# 2_Microcontrolador.net
KiCad netlist of a schematic drawn in Altium Designer
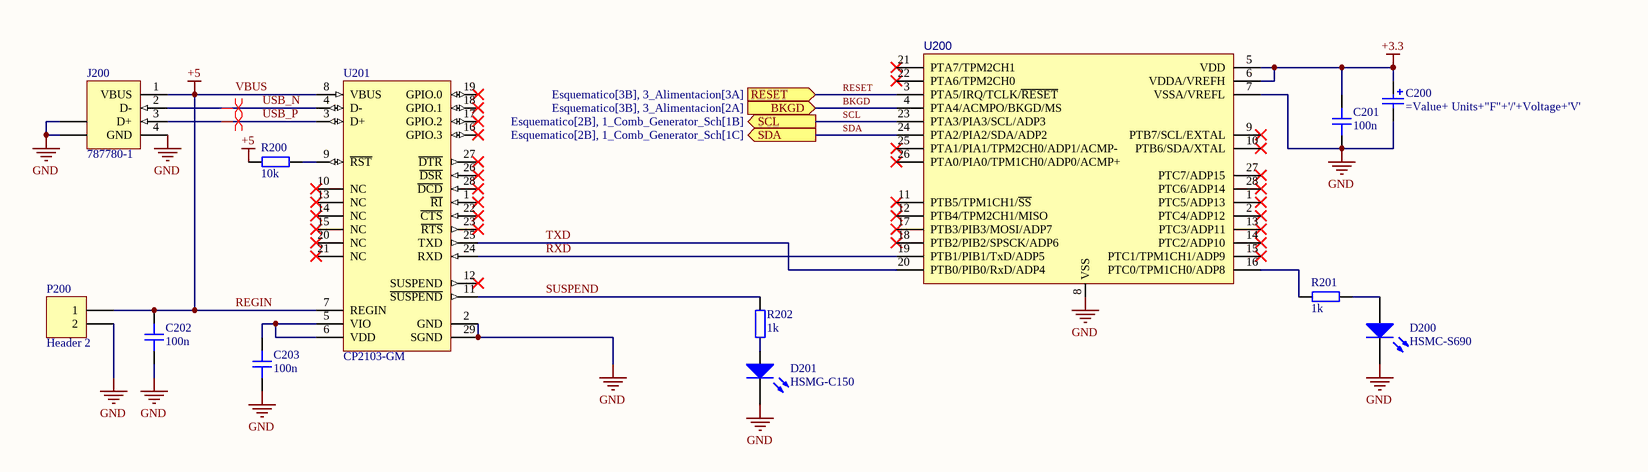
[diagram p0: 2_Microcontrolador.SchDoc]

(export (version "E")
  (design (tool "Eeschema 10.0.6"))
  (components
    (comp (ref "C200")
      (value "47u/16V")
      (footprint "C SIZE SMD CAPACITOR")
      (description "Capacitor Electr. Alum. SMD WxLxH 6.3x6.3x5.3 Ǿ= 6 mm")
      (fields
        (field (name "MANUFACTURER") "Generic Components")
        (field (name "VOLTAGE") "16")
        (field (name "PUBLISHER") "Altium Hobart Technology Centre")
      )
      (libsource (lib "COMB GEN 1") (part "Cap Pol1"))
    )
    (comp (ref "C201")
      (value "100n")
      (footprint "CAP_0603")
      (description "Capacitor SMD 0603")
      (libsource (lib "Schematic-Lib-PhilsLab") (part "CAP_0603"))
    )
    (comp (ref "C202")
      (value "100n")
      (footprint "CAP_0603")
      (description "Capacitor SMD 0603")
      (libsource (lib "Schematic-Lib-PhilsLab") (part "CAP_0603"))
    )
    (comp (ref "C203")
      (value "100n")
      (footprint "CAP_0603")
      (description "Capacitor SMD 0603")
      (libsource (lib "Schematic-Lib-PhilsLab") (part "CAP_0603"))
    )
    (comp (ref "D200")
      (value "HSMC-S690")
      (footprint "1.6X0.8X0.7")
      (description "SMT Top Mount Chip LED, Red")
      (fields (field (name "PUBLISHER") "Altium Limited"))
      (libsource (lib "Agilent Optoelectronic LED") (part "HSMC-S690"))
    )
    (comp (ref "D201")
      (value "HSMG-C150")
      (footprint "3.2X1.6X1.1")
      (description "Surface Mount Chip LED, Green")
      (fields (field (name "PUBLISHER") "Altium Limited"))
      (libsource (lib "Agilent Optoelectronic LED") (part "HSMG-C150"))
    )
    (comp (ref "J200")
      (value "787780-1")
      (footprint "USB 787780")
      (description "USB 1.1, Right Angle, Thru-Hole, B Type, Receptacle, 4 Position, Black")
      (fields (field (name "PUBLISHER") "Altium Limited"))
      (libsource (lib "AMP Serial Bus USB") (part "787780-1"))
    )
    (comp (ref "P200")
      (value "Header 2")
      (footprint "HDR1X2")
      (description "Header, 2-Pin")
      (fields (field (name "PUBLISHER") "Altium Limited"))
      (libsource (lib "Miscellaneous Connectors") (part "Header 2"))
    )
    (comp (ref "R200")
      (value "10k")
      (footprint "RES_0603")
      (description "Resistor SMD 0603")
      (libsource (lib "Schematic-Lib-PhilsLab") (part "RES_0603"))
    )
    (comp (ref "R201")
      (value "1k")
      (footprint "RES_0603")
      (description "Resistor SMD 0603")
      (libsource (lib "Schematic-Lib-PhilsLab") (part "RES_0603"))
    )
    (comp (ref "R202")
      (value "1k")
      (footprint "RES_0603")
      (description "Resistor SMD 0603")
      (libsource (lib "Schematic-Lib-PhilsLab") (part "RES_0603"))
    )
    (comp (ref "U200")
      (value "~")
      (footprint "TSSOP28_25.5_295_15X58_SMD")
      (description "IC MCU 8BIT 32KB FLASH 28TSSOP\r\nWITH AUTO-DIRECTION SENSING AND ±15-kV ESD PROTECTION")
      (fields
        (field (name "PART NUMBER") "MC9S08SH32CTL_TSSOP28")
        (field (name "MANUFACTURER") "NXP USA Inc.")
      )
      (libsource (lib "COMB GEN") (part "MC9S08SH32CTL"))
    )
    (comp (ref "U201")
      (value "CP2103-GM")
      (footprint "SLAB-QFN-28-3125x3125TP_A_N")
      (description "Single-Chip USB to UART Bridge, 1024 Bytes EEPROM, -40 to 85 degC, 28-pin QFN, Tube")
      (fields (field (name "MANUFACTURER") "Silicon Labs"))
      (libsource (lib "Silicon Labs Interface") (part "CP2103-GM"))
    )
  )
  (nets
    (net (code "1") (name "+3.3") (class "Default")
      (node (ref "C200") (pin "1") (pinfunction "1_1") (pintype "passive"))
      (node (ref "C201") (pin "1") (pinfunction "1_1") (pintype "passive"))
      (node (ref "U200") (pin "5") (pinfunction "VDD_5") (pintype "passive"))
      (node (ref "U200") (pin "6") (pinfunction "VDDA/VREFH_6") (pintype "passive"))
    )
    (net (code "2") (name "+5") (class "Default")
      (node (ref "C202") (pin "1") (pinfunction "1_1") (pintype "passive"))
      (node (ref "J200") (pin "1") (pinfunction "VBUS_1") (pintype "power_in"))
      (node (ref "P200") (pin "1") (pinfunction "1_1") (pintype "passive"))
      (node (ref "R200") (pin "2") (pinfunction "2_2") (pintype "passive"))
      (node (ref "U201") (pin "7") (pinfunction "REGIN_7") (pintype "power_in"))
      (node (ref "U201") (pin "8") (pinfunction "VBUS_8") (pintype "input"))
    )
    (net (code "3") (name "/BKGD") (class "Default")
      (node (ref "U200") (pin "4") (pinfunction "PTA4/ACMPO/BKGD/MS_4") (pintype "passive"))
    )
    (net (code "4") (name "/RESET") (class "Default")
      (node (ref "U200") (pin "3") (pinfunction "PTA5/IRQ/TCLK/~{RESET}_3") (pintype "passive"))
    )
    (net (code "5") (name "/RXD") (class "Default")
      (node (ref "U200") (pin "19") (pinfunction "PTB1/PIB1/TxD/ADP5_19") (pintype "passive"))
      (node (ref "U201") (pin "24") (pinfunction "RXD_24") (pintype "input"))
    )
    (net (code "6") (name "/SCL") (class "Default")
      (node (ref "U200") (pin "23") (pinfunction "PTA3/PIA3/SCL/ADP3_23") (pintype "passive"))
    )
    (net (code "7") (name "/SDA") (class "Default")
      (node (ref "U200") (pin "24") (pinfunction "PTA2/PIA2/SDA/ADP2_24") (pintype "passive"))
    )
    (net (code "8") (name "/SUSPEND") (class "Default")
      (node (ref "R202") (pin "1") (pinfunction "1_1") (pintype "passive"))
      (node (ref "U201") (pin "11") (pinfunction "~{SUSPEND}_11") (pintype "output"))
    )
    (net (code "9") (name "/TXD") (class "Default")
      (node (ref "U200") (pin "20") (pinfunction "PTB0/PIB0/RxD/ADP4_20") (pintype "passive"))
      (node (ref "U201") (pin "25") (pinfunction "TXD_25") (pintype "output"))
    )
    (net (code "10") (name "/USB_N") (class "Default")
      (node (ref "J200") (pin "2") (pinfunction "D-_2") (pintype "input"))
      (node (ref "U201") (pin "4") (pinfunction "D-_4") (pintype "bidirectional"))
    )
    (net (code "11") (name "/USB_P") (class "Default")
      (node (ref "J200") (pin "3") (pinfunction "D+_3") (pintype "input"))
      (node (ref "U201") (pin "3") (pinfunction "D+_3") (pintype "bidirectional"))
    )
    (net (code "12") (name "GND") (class "Default")
      (node (ref "C200") (pin "2") (pinfunction "2_2") (pintype "passive"))
      (node (ref "C201") (pin "2") (pinfunction "2_2") (pintype "passive"))
      (node (ref "C202") (pin "2") (pinfunction "2_2") (pintype "passive"))
      (node (ref "C203") (pin "2") (pinfunction "2_2") (pintype "passive"))
      (node (ref "D200") (pin "2") (pinfunction "K_2") (pintype "passive"))
      (node (ref "D201") (pin "2") (pinfunction "K_2") (pintype "passive"))
      (node (ref "J200") (pin "4") (pinfunction "GND_4") (pintype "power_in"))
      (node (ref "J200") (pin "5") (pinfunction "SHLD_5") (pintype "passive"))
      (node (ref "J200") (pin "6") (pinfunction "SHLD_6") (pintype "passive"))
      (node (ref "P200") (pin "2") (pinfunction "2_2") (pintype "passive"))
      (node (ref "U200") (pin "7") (pinfunction "VSSA/VREFL_7") (pintype "passive"))
      (node (ref "U200") (pin "8") (pinfunction "VSS_8") (pintype "passive"))
      (node (ref "U201") (pin "2") (pinfunction "GND_2") (pintype "power_in"))
      (node (ref "U201") (pin "29") (pinfunction "SGND_29") (pintype "power_in"))
    )
    (net (code "13") (name "Net-(D200-A)") (class "Default")
      (node (ref "D200") (pin "1") (pinfunction "A_1") (pintype "passive"))
      (node (ref "R201") (pin "2") (pinfunction "2_2") (pintype "passive"))
    )
    (net (code "14") (name "Net-(D201-A)") (class "Default")
      (node (ref "D201") (pin "1") (pinfunction "A_1") (pintype "passive"))
      (node (ref "R202") (pin "2") (pinfunction "2_2") (pintype "passive"))
    )
    (net (code "15") (name "Net-(U200-PTC0{slash}TPM1CH0{slash}ADP8)") (class "Default")
      (node (ref "R201") (pin "1") (pinfunction "1_1") (pintype "passive"))
      (node (ref "U200") (pin "16") (pinfunction "PTC0/TPM1CH0/ADP8_16") (pintype "passive"))
    )
    (net (code "16") (name "Net-(U201-VDD)") (class "Default")
      (node (ref "C203") (pin "1") (pinfunction "1_1") (pintype "passive"))
      (node (ref "U201") (pin "5") (pinfunction "VIO_5") (pintype "power_in"))
      (node (ref "U201") (pin "6") (pinfunction "VDD_6") (pintype "power_in"))
    )
    (net (code "17") (name "Net-(U201-~{RST})") (class "Default")
      (node (ref "R200") (pin "1") (pinfunction "1_1") (pintype "passive"))
      (node (ref "U201") (pin "9") (pinfunction "~{RST}_9") (pintype "bidirectional"))
    )
    (net (code "18") (name "unconnected-(U200-PTA0{slash}PIA0{slash}TPM1CH0{slash}ADP0{slash}ACMP+-Pad26)") (class "Default")
      (node (ref "U200") (pin "26") (pinfunction "PTA0/PIA0/TPM1CH0/ADP0/ACMP+_26") (pintype "passive+no_connect"))
    )
    (net (code "19") (name "unconnected-(U200-PTA1{slash}PIA1{slash}TPM2CH0{slash}ADP1{slash}ACMP--Pad25)") (class "Default")
      (node (ref "U200") (pin "25") (pinfunction "PTA1/PIA1/TPM2CH0/ADP1/ACMP-_25") (pintype "passive+no_connect"))
    )
    (net (code "20") (name "unconnected-(U200-PTA6{slash}TPM2CH0-Pad22)") (class "Default")
      (node (ref "U200") (pin "22") (pinfunction "PTA6/TPM2CH0_22") (pintype "passive+no_connect"))
    )
    (net (code "21") (name "unconnected-(U200-PTA7{slash}TPM2CH1-Pad21)") (class "Default")
      (node (ref "U200") (pin "21") (pinfunction "PTA7/TPM2CH1_21") (pintype "passive+no_connect"))
    )
    (net (code "22") (name "unconnected-(U200-PTB2{slash}PIB2{slash}SPSCK{slash}ADP6-Pad18)") (class "Default")
      (node (ref "U200") (pin "18") (pinfunction "PTB2/PIB2/SPSCK/ADP6_18") (pintype "passive+no_connect"))
    )
    (net (code "23") (name "unconnected-(U200-PTB3{slash}PIB3{slash}MOSI{slash}ADP7-Pad17)") (class "Default")
      (node (ref "U200") (pin "17") (pinfunction "PTB3/PIB3/MOSI/ADP7_17") (pintype "passive+no_connect"))
    )
    (net (code "24") (name "unconnected-(U200-PTB4{slash}TPM2CH1{slash}MISO-Pad12)") (class "Default")
      (node (ref "U200") (pin "12") (pinfunction "PTB4/TPM2CH1/MISO_12") (pintype "passive+no_connect"))
    )
    (net (code "25") (name "unconnected-(U200-PTB5{slash}TPM1CH1{slash}~{SS}-Pad11)") (class "Default")
      (node (ref "U200") (pin "11") (pinfunction "PTB5/TPM1CH1/~{SS}_11") (pintype "passive+no_connect"))
    )
    (net (code "26") (name "unconnected-(U200-PTB6{slash}SDA{slash}XTAL-Pad10)") (class "Default")
      (node (ref "U200") (pin "10") (pinfunction "PTB6/SDA/XTAL_10") (pintype "passive+no_connect"))
    )
    (net (code "27") (name "unconnected-(U200-PTB7{slash}SCL{slash}EXTAL-Pad9)") (class "Default")
      (node (ref "U200") (pin "9") (pinfunction "PTB7/SCL/EXTAL_9") (pintype "passive+no_connect"))
    )
    (net (code "28") (name "unconnected-(U200-PTC1{slash}TPM1CH1{slash}ADP9-Pad15)") (class "Default")
      (node (ref "U200") (pin "15") (pinfunction "PTC1/TPM1CH1/ADP9_15") (pintype "passive+no_connect"))
    )
    (net (code "29") (name "unconnected-(U200-PTC2{slash}ADP10-Pad14)") (class "Default")
      (node (ref "U200") (pin "14") (pinfunction "PTC2/ADP10_14") (pintype "passive+no_connect"))
    )
    (net (code "30") (name "unconnected-(U200-PTC3{slash}ADP11-Pad13)") (class "Default")
      (node (ref "U200") (pin "13") (pinfunction "PTC3/ADP11_13") (pintype "passive+no_connect"))
    )
    (net (code "31") (name "unconnected-(U200-PTC4{slash}ADP12-Pad2)") (class "Default")
      (node (ref "U200") (pin "2") (pinfunction "PTC4/ADP12_2") (pintype "passive+no_connect"))
    )
    (net (code "32") (name "unconnected-(U200-PTC5{slash}ADP13-Pad1)") (class "Default")
      (node (ref "U200") (pin "1") (pinfunction "PTC5/ADP13_1") (pintype "passive+no_connect"))
    )
    (net (code "33") (name "unconnected-(U200-PTC6{slash}ADP14-Pad28)") (class "Default")
      (node (ref "U200") (pin "28") (pinfunction "PTC6/ADP14_28") (pintype "passive+no_connect"))
    )
    (net (code "34") (name "unconnected-(U200-PTC7{slash}ADP15-Pad27)") (class "Default")
      (node (ref "U200") (pin "27") (pinfunction "PTC7/ADP15_27") (pintype "passive+no_connect"))
    )
    (net (code "35") (name "unconnected-(U201-GPIO.0-Pad19)") (class "Default")
      (node (ref "U201") (pin "19") (pinfunction "GPIO.0_19") (pintype "bidirectional+no_connect"))
    )
    (net (code "36") (name "unconnected-(U201-GPIO.1-Pad18)") (class "Default")
      (node (ref "U201") (pin "18") (pinfunction "GPIO.1_18") (pintype "bidirectional+no_connect"))
    )
    (net (code "37") (name "unconnected-(U201-GPIO.2-Pad17)") (class "Default")
      (node (ref "U201") (pin "17") (pinfunction "GPIO.2_17") (pintype "bidirectional+no_connect"))
    )
    (net (code "38") (name "unconnected-(U201-GPIO.3-Pad16)") (class "Default")
      (node (ref "U201") (pin "16") (pinfunction "GPIO.3_16") (pintype "bidirectional+no_connect"))
    )
    (net (code "39") (name "unconnected-(U201-NC-Pad10)") (class "Default")
      (node (ref "U201") (pin "10") (pinfunction "NC_10") (pintype "passive+no_connect"))
    )
    (net (code "40") (name "unconnected-(U201-NC-Pad13)") (class "Default")
      (node (ref "U201") (pin "13") (pinfunction "NC_13") (pintype "passive+no_connect"))
    )
    (net (code "41") (name "unconnected-(U201-NC-Pad14)") (class "Default")
      (node (ref "U201") (pin "14") (pinfunction "NC_14") (pintype "passive+no_connect"))
    )
    (net (code "42") (name "unconnected-(U201-NC-Pad15)") (class "Default")
      (node (ref "U201") (pin "15") (pinfunction "NC_15") (pintype "passive+no_connect"))
    )
    (net (code "43") (name "unconnected-(U201-NC-Pad20)") (class "Default")
      (node (ref "U201") (pin "20") (pinfunction "NC_20") (pintype "passive+no_connect"))
    )
    (net (code "44") (name "unconnected-(U201-NC-Pad21)") (class "Default")
      (node (ref "U201") (pin "21") (pinfunction "NC_21") (pintype "passive+no_connect"))
    )
    (net (code "45") (name "unconnected-(U201-SUSPEND-Pad12)") (class "Default")
      (node (ref "U201") (pin "12") (pinfunction "SUSPEND_12") (pintype "output+no_connect"))
    )
    (net (code "46") (name "unconnected-(U201-~{CTS}-Pad22)") (class "Default")
      (node (ref "U201") (pin "22") (pinfunction "~{CTS}_22") (pintype "input+no_connect"))
    )
    (net (code "47") (name "unconnected-(U201-~{DCD}-Pad28)") (class "Default")
      (node (ref "U201") (pin "28") (pinfunction "~{DCD}_28") (pintype "input+no_connect"))
    )
    (net (code "48") (name "unconnected-(U201-~{DSR}-Pad26)") (class "Default")
      (node (ref "U201") (pin "26") (pinfunction "~{DSR}_26") (pintype "input+no_connect"))
    )
    (net (code "49") (name "unconnected-(U201-~{DTR}-Pad27)") (class "Default")
      (node (ref "U201") (pin "27") (pinfunction "~{DTR}_27") (pintype "output+no_connect"))
    )
    (net (code "50") (name "unconnected-(U201-~{RI}-Pad1)") (class "Default")
      (node (ref "U201") (pin "1") (pinfunction "~{RI}_1") (pintype "input+no_connect"))
    )
    (net (code "51") (name "unconnected-(U201-~{RTS}-Pad23)") (class "Default")
      (node (ref "U201") (pin "23") (pinfunction "~{RTS}_23") (pintype "output+no_connect"))
    )
  )
)
